# kilif_rev1.net
KiCad netlist of a schematic drawn in Altium Designer
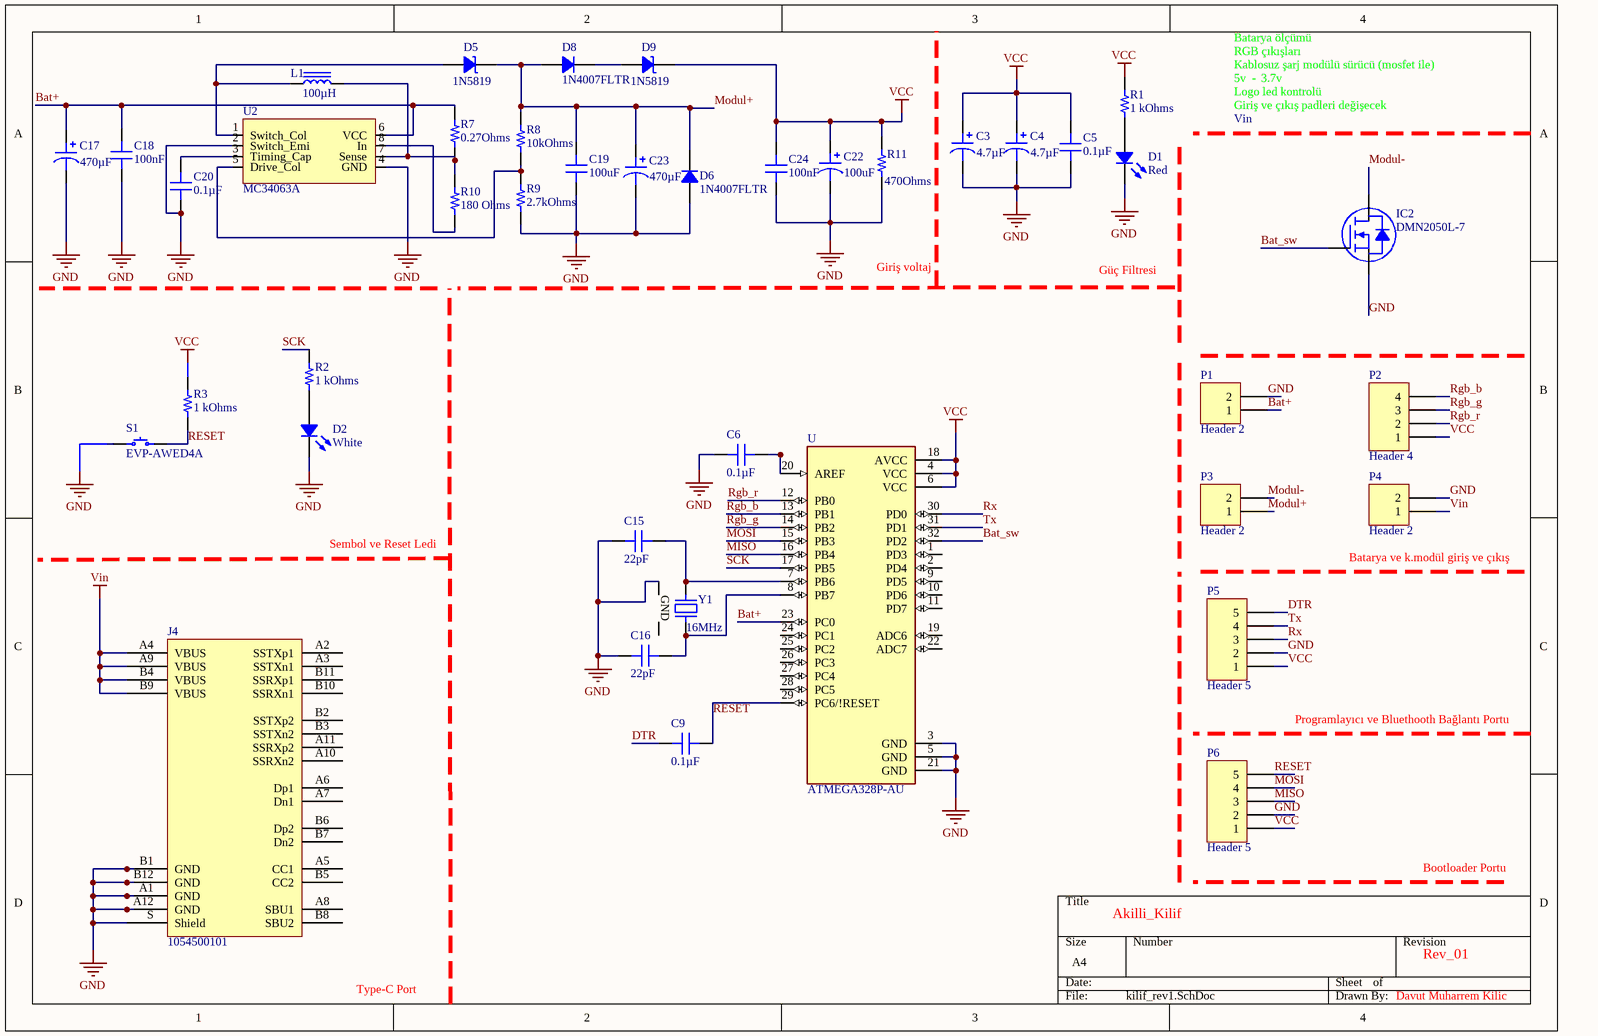
[diagram p0: kilif_rev1.SchDoc]

(export (version "E")
  (design (tool "Eeschema 10.0.6"))
  (components
    (comp (ref "C3")
      (value "4.7µF")
      (footprint "CAP POL 1206_3216")
      (description "CAP TANT POLY 4.7UF 10V 1206")
      (fields (field (name "PART NUMBER") "T55A475M010C0500") (field (name "MANUFACTURER") "Vishay Sprague"))
      (libsource (lib "Celestial Altium Library - altium_library") (part "Polarised Capacitor"))
    )
    (comp (ref "C4")
      (value "4.7µF")
      (footprint "CAP POL 1206_3216")
      (description "CAP TANT POLY 4.7UF 10V 1206")
      (fields (field (name "PART NUMBER") "T55A475M010C0500") (field (name "MANUFACTURER") "Vishay Sprague"))
      (libsource (lib "Celestial Altium Library - altium_library") (part "Polarised Capacitor"))
    )
    (comp (ref "C5")
      (value "0.1µF")
      (footprint "CAP 0603_1608")
      (description "CAP CER 0.1UF 50V X7R 0603")
      (fields (field (name "PART NUMBER") "C0603C104K5RAC7411") (field (name "MANUFACTURER") "KEMET"))
      (libsource (lib "Celestial Altium Library - altium_library") (part "Capacitor"))
    )
    (comp (ref "C6")
      (value "0.1µF")
      (footprint "CAP 0603_1608")
      (description "CAP CER 0.1UF 16V X7R 0603")
      (fields (field (name "PART NUMBER") "CS0603KRX7R7BB104") (field (name "MANUFACTURER") "Yageo"))
      (libsource (lib "Celestial Altium Library - altium_library") (part "Capacitor"))
    )
    (comp (ref "C9")
      (value "0.1µF")
      (footprint "CAP 0603_1608")
      (description "CAP CER 0.1UF 50V X7R 0603")
      (fields (field (name "PART NUMBER") "C0603C104K5RAC7411") (field (name "MANUFACTURER") "KEMET"))
      (libsource (lib "Celestial Altium Library - altium_library") (part "Capacitor"))
    )
    (comp (ref "C15")
      (value "22pF")
      (footprint "CAP 0603_1608")
      (description "CAP CER 22PfF 50V X7R 0603")
      (fields (field (name "PART NUMBER") "C0603C104K5RAC7411") (field (name "MANUFACTURER") "KEMET"))
      (libsource (lib "Celestial Altium Library - altium_library") (part "Capacitor"))
    )
    (comp (ref "C16")
      (value "22pF")
      (footprint "CAP 0603_1608")
      (description "CAP CER 22PF 50V X7R 0603")
      (fields (field (name "PART NUMBER") "C0603C104K5RAC7411") (field (name "MANUFACTURER") "KEMET"))
      (libsource (lib "Celestial Altium Library - altium_library") (part "Capacitor"))
    )
    (comp (ref "C17")
      (value "470µF")
      (footprint "CAP POL 1206_3216")
      (description "CAP TANT POLY 4.7UF 10V 1206")
      (fields (field (name "PART NUMBER") "T55A475M010C0500") (field (name "MANUFACTURER") "Vishay Sprague"))
      (libsource (lib "Celestial Altium Library - altium_library") (part "Polarised Capacitor"))
    )
    (comp (ref "C18")
      (value "100nF")
      (footprint "CAP 0603_1608")
      (description "CAP CER 0.1UF 50V X7R 0603")
      (fields (field (name "PART NUMBER") "C0603C104K5RAC7411") (field (name "MANUFACTURER") "KEMET"))
      (libsource (lib "Celestial Altium Library - altium_library") (part "Capacitor"))
    )
    (comp (ref "C19")
      (value "100uF")
      (footprint "CAP 0603_1608")
      (description "CAP CER 0.1UF 50V X7R 0603")
      (fields (field (name "PART NUMBER") "C0603C104K5RAC7411") (field (name "MANUFACTURER") "KEMET"))
      (libsource (lib "Celestial Altium Library - altium_library") (part "Capacitor"))
    )
    (comp (ref "C20")
      (value "0.1µF")
      (footprint "CAP 0603_1608")
      (description "CAP CER 0.1UF 50V X7R 0603")
      (fields (field (name "PART NUMBER") "C0603C104K5RAC7411") (field (name "MANUFACTURER") "KEMET"))
      (libsource (lib "Celestial Altium Library - altium_library") (part "Capacitor"))
    )
    (comp (ref "C22")
      (value "100uF")
      (footprint "CAP POL 1206_3216")
      (description "CAP TANT POLY 4.7UF 10V 1206")
      (fields (field (name "PART NUMBER") "T55A475M010C0500") (field (name "MANUFACTURER") "Vishay Sprague"))
      (libsource (lib "Celestial Altium Library - altium_library") (part "Polarised Capacitor"))
    )
    (comp (ref "C23")
      (value "470µF")
      (footprint "CAP POL 1206_3216")
      (description "CAP TANT POLY 4.7UF 10V 1206")
      (fields (field (name "PART NUMBER") "T55A475M010C0500") (field (name "MANUFACTURER") "Vishay Sprague"))
      (libsource (lib "Celestial Altium Library - altium_library") (part "Polarised Capacitor"))
    )
    (comp (ref "C24")
      (value "100nF")
      (footprint "CAP 0603_1608")
      (description "CAP CER 0.1UF 50V X7R 0603")
      (fields (field (name "PART NUMBER") "C0603C104K5RAC7411") (field (name "MANUFACTURER") "KEMET"))
      (libsource (lib "Celestial Altium Library - altium_library") (part "Capacitor"))
    )
    (comp (ref "D1")
      (value "Red")
      (footprint "LED 0805_2012 RED")
      (description "LED RED CLEAR 2SMD")
      (fields
        (field (name "PART NUMBER") "EAST2012RA1")
        (field (name "MANUFACTURER") "Everlight Electronics Co Ltd")
      )
      (libsource (lib "Celestial Altium Library - altium_library") (part "LED"))
    )
    (comp (ref "D2")
      (value "White")
      (footprint "LED 1206_3216")
      (description "LED WHITE 1206 SMD")
      (fields (field (name "PART NUMBER") "LTW-C230DS") (field (name "MANUFACTURER") "Lite-On Inc."))
      (libsource (lib "Celestial Altium Library - altium_library") (part "LED"))
    )
    (comp (ref "D5")
      (value "1N5819")
      (footprint "SMF DO-219AB")
      (description "TVS DIODE 45V 72.7V DO219AB")
      (fields
        (field (name "PART NUMBER") "SMF45A-E3-08")
        (field (name "MANUFACTURER") "Vishay Semiconductor Diodes Division")
      )
      (libsource (lib "Celestial Altium Library - altium_library") (part "DIODE TVS UNI"))
    )
    (comp (ref "D6")
      (value "1N4007FLTR")
      (footprint "SOD123F")
      (description "STANDARD RECTIFIER 1000V SOD-123")
      (fields (field (name "MANUFACTURER") "SMC Diode Solutions"))
      (libsource (lib "Celestial Altium Library - altium_library") (part "Diode"))
    )
    (comp (ref "D8")
      (value "1N4007FLTR")
      (footprint "SOD123F")
      (description "STANDARD RECTIFIER 1000V SOD-123")
      (fields (field (name "MANUFACTURER") "SMC Diode Solutions"))
      (libsource (lib "Celestial Altium Library - altium_library") (part "Diode"))
    )
    (comp (ref "D9")
      (value "1N5819")
      (footprint "SMF DO-219AB")
      (description "TVS DIODE 45V 72.7V DO219AB")
      (fields
        (field (name "PART NUMBER") "SMF45A-E3-08")
        (field (name "MANUFACTURER") "Vishay Semiconductor Diodes Division")
      )
      (libsource (lib "Celestial Altium Library - altium_library") (part "DIODE TVS UNI"))
    )
    (comp (ref "IC2")
      (value "DMN2050L-7")
      (footprint "DIODES SOT-23-3")
      (description "MOSFET N-CH 20V 5.9A SOT23-3")
      (fields (field (name "MANUFACTURER") "Diodes Incorporated"))
      (libsource (lib "Celestial Altium Library - altium_library") (part "DIODES INC MOSFET N-CH SOT-23-3"))
    )
    (comp (ref "J4")
      (value "1054500101")
      (footprint "Molex 1054500101")
      (description "CONN RCP USB3.1 TYPEC 24P SMD RA")
      (fields (field (name "MANUFACTURER") "Molex"))
      (libsource (lib "Celestial Altium Library - altium_library") (part "USB 3.0 Type C"))
    )
    (comp (ref "L1")
      (value "100µH")
      (footprint "TDK VLCF4028-2")
      (description "FIXED IND 100UH 330MA 670 MOHM")
      (fields
        (field (name "PART NUMBER") "VLCF5028T-101MR33-2")
        (field (name "MANUFACTURER") "TDK Corporation")
      )
      (libsource (lib "Celestial Altium Library - altium_library") (part "Inductor"))
    )
    (comp (ref "P1")
      (value "Header 2")
      (footprint "HDR1X2")
      (description "Header, 2-Pin")
      (fields (field (name "PUBLISHER") "Altium Limited"))
      (libsource (lib "Miscellaneous Connectors") (part "Header 2"))
    )
    (comp (ref "P2")
      (value "Header 4")
      (footprint "HDR1X4")
      (description "Header, 4-Pin")
      (fields (field (name "PUBLISHER") "Altium Limited"))
      (libsource (lib "Miscellaneous Connectors") (part "Header 4"))
    )
    (comp (ref "P3")
      (value "Header 2")
      (footprint "HDR1X2")
      (description "Header, 2-Pin")
      (fields (field (name "PUBLISHER") "Altium Limited"))
      (libsource (lib "Miscellaneous Connectors") (part "Header 2"))
    )
    (comp (ref "P4")
      (value "Header 2")
      (footprint "HDR1X2")
      (description "Header, 2-Pin")
      (fields (field (name "PUBLISHER") "Altium Limited"))
      (libsource (lib "Miscellaneous Connectors") (part "Header 2"))
    )
    (comp (ref "P5")
      (value "Header 5")
      (footprint "HDR1X5")
      (description "Header, 5-Pin")
      (fields (field (name "PUBLISHER") "Altium Limited"))
      (libsource (lib "Miscellaneous Connectors") (part "Header 5"))
    )
    (comp (ref "P6")
      (value "Header 5")
      (footprint "HDR1X5")
      (description "Header, 5-Pin")
      (fields (field (name "PUBLISHER") "Altium Limited"))
      (libsource (lib "Miscellaneous Connectors") (part "Header 5"))
    )
    (comp (ref "R1")
      (value "1 kOhms")
      (footprint "RES 0805_2012")
      (description "RES 1K OHM 1% 1/4W 0805")
      (fields
        (field (name "PART NUMBER") "RNCP0805FTD1K00")
        (field (name "MANUFACTURER") "Stackpole Electronics Inc")
      )
      (libsource (lib "Celestial Altium Library - altium_library") (part "Resistor"))
    )
    (comp (ref "R2")
      (value "1 kOhms")
      (footprint "RES 0805_2012")
      (description "RES 1K OHM 1% 1/4W 0805")
      (fields
        (field (name "PART NUMBER") "RNCP0805FTD1K00")
        (field (name "MANUFACTURER") "Stackpole Electronics Inc")
      )
      (libsource (lib "Celestial Altium Library - altium_library") (part "Resistor"))
    )
    (comp (ref "R3")
      (value "1 kOhms")
      (footprint "RES 0805_2012")
      (description "RES 1K OHM 1% 1/4W 0805")
      (fields
        (field (name "PART NUMBER") "RNCP0805FTD1K00")
        (field (name "MANUFACTURER") "Stackpole Electronics Inc")
      )
      (libsource (lib "Celestial Altium Library - altium_library") (part "Resistor"))
    )
    (comp (ref "R7")
      (value "0.27Ohms")
      (footprint "RES 0805_2012")
      (description "RES 1K OHM 1% 1/4W 0805")
      (fields
        (field (name "PART NUMBER") "RNCP0805FTD1K00")
        (field (name "MANUFACTURER") "Stackpole Electronics Inc")
      )
      (libsource (lib "Celestial Altium Library - altium_library") (part "Resistor"))
    )
    (comp (ref "R8")
      (value "10kOhms")
      (footprint "RES 0805_2012")
      (description "RES 1K OHM 1% 1/4W 0805")
      (fields
        (field (name "PART NUMBER") "RNCP0805FTD1K00")
        (field (name "MANUFACTURER") "Stackpole Electronics Inc")
      )
      (libsource (lib "Celestial Altium Library - altium_library") (part "Resistor"))
    )
    (comp (ref "R9")
      (value "2.7kOhms")
      (footprint "RES 0805_2012")
      (description "RES 1K OHM 1% 1/4W 0805")
      (fields
        (field (name "PART NUMBER") "RNCP0805FTD1K00")
        (field (name "MANUFACTURER") "Stackpole Electronics Inc")
      )
      (libsource (lib "Celestial Altium Library - altium_library") (part "Resistor"))
    )
    (comp (ref "R10")
      (value "180 Ohms")
      (footprint "RES 0805_2012")
      (description "RES 1K OHM 1% 1/4W 0805")
      (fields
        (field (name "PART NUMBER") "RNCP0805FTD1K00")
        (field (name "MANUFACTURER") "Stackpole Electronics Inc")
      )
      (libsource (lib "Celestial Altium Library - altium_library") (part "Resistor"))
    )
    (comp (ref "R11")
      (value "470Ohms")
      (footprint "RES 0805_2012")
      (description "RES 1K OHM 1% 1/4W 0805")
      (fields
        (field (name "PART NUMBER") "RNCP0805FTD1K00")
        (field (name "MANUFACTURER") "Stackpole Electronics Inc")
      )
      (libsource (lib "Celestial Altium Library - altium_library") (part "Resistor"))
    )
    (comp (ref "S1")
      (value "EVP-AWED4A")
      (footprint "PANASONIC EVPAW")
      (description "3.0MM X 2.0MM / 3.3N / 0.15MM ST")
      (fields (field (name "MANUFACTURER") "Panasonic Electronic Components"))
      (libsource (lib "Celestial Altium Library - altium_library") (part "SPST-NO 2 PIN"))
    )
    (comp (ref "U")
      (value "ATMEGA328P-AU")
      (footprint "QFP80P900X900X120-32N")
      (description "AVR AVRÂ® ATmega Microcontroller IC 8-Bit 20MHz 32KB _16K x 16_ FLASH 32-TQFP _7x7_")
      (fields (field (name "MF") "Microchip"))
      (libsource (lib "ATMEGA328P-AU") (part "ATMEGA328P-AU"))
    )
    (comp (ref "U2")
      (value "MC34063A")
      (footprint "MC34063A,SOIC127P600X140-8N")
      (description "1.5 A, Step-Up/Down/\r\nInverting Switching\r\nRegulators")
      (libsource (lib "Schlib1") (part "MC34063A"))
    )
    (comp (ref "Y1")
      (value "16MHz")
      (footprint "NDK NX3225SA")
      (description "CRYSTAL 16.0000MHZ 8PF SMD")
      (fields
        (field (name "PART NUMBER") "NX3225SA-16.000M-STD-CRS-2")
        (field (name "MANUFACTURER") "NDK America, Inc.")
      )
      (libsource (lib "Celestial Altium Library - altium_library") (part "NDK Crystal NX3225SA"))
    )
  )
  (nets
    (net (code "1") (name "/Bat+") (class "Default")
      (node (ref "C17") (pin "1") (pinfunction "1_1") (pintype "passive"))
      (node (ref "C18") (pin "2") (pinfunction "2_2") (pintype "passive"))
      (node (ref "P1") (pin "1") (pinfunction "1_1") (pintype "passive"))
      (node (ref "R7") (pin "2") (pinfunction "2_2") (pintype "passive"))
      (node (ref "U") (pin "23") (pinfunction "PC0_23") (pintype "bidirectional"))
      (node (ref "U2") (pin "6") (pinfunction "VCC_6") (pintype "passive"))
    )
    (net (code "2") (name "/Bat_sw") (class "Default")
      (node (ref "IC2") (pin "1") (pinfunction "G_1") (pintype "passive"))
      (node (ref "U") (pin "32") (pinfunction "PD2_32") (pintype "bidirectional"))
    )
    (net (code "3") (name "/DTR") (class "Default")
      (node (ref "C9") (pin "2") (pinfunction "2_2") (pintype "passive"))
      (node (ref "P5") (pin "5") (pinfunction "5_5") (pintype "passive"))
    )
    (net (code "4") (name "/MISO") (class "Default")
      (node (ref "P6") (pin "3") (pinfunction "3_3") (pintype "passive"))
      (node (ref "U") (pin "16") (pinfunction "PB4_16") (pintype "bidirectional"))
    )
    (net (code "5") (name "/MOSI") (class "Default")
      (node (ref "P6") (pin "4") (pinfunction "4_4") (pintype "passive"))
      (node (ref "U") (pin "15") (pinfunction "PB3_15") (pintype "bidirectional"))
    )
    (net (code "6") (name "/Modul+") (class "Default")
      (node (ref "C19") (pin "2") (pinfunction "2_2") (pintype "passive"))
      (node (ref "C23") (pin "1") (pinfunction "1_1") (pintype "passive"))
      (node (ref "D5") (pin "2") (pinfunction "2_2") (pintype "passive"))
      (node (ref "D6") (pin "2") (pinfunction "2_2") (pintype "passive"))
      (node (ref "D8") (pin "1") (pinfunction "1_1") (pintype "passive"))
      (node (ref "P3") (pin "1") (pinfunction "1_1") (pintype "passive"))
      (node (ref "R8") (pin "2") (pinfunction "2_2") (pintype "passive"))
    )
    (net (code "7") (name "/Modul-") (class "Default")
      (node (ref "IC2") (pin "3") (pinfunction "D_3") (pintype "passive"))
      (node (ref "P3") (pin "2") (pinfunction "2_2") (pintype "passive"))
    )
    (net (code "8") (name "/RESET") (class "Default")
      (node (ref "C9") (pin "1") (pinfunction "1_1") (pintype "passive"))
      (node (ref "P6") (pin "5") (pinfunction "5_5") (pintype "passive"))
      (node (ref "R3") (pin "1") (pinfunction "1_1") (pintype "passive"))
      (node (ref "S1") (pin "2") (pinfunction "2_2") (pintype "passive"))
      (node (ref "U") (pin "29") (pinfunction "PC6/!RESET_29") (pintype "bidirectional"))
    )
    (net (code "9") (name "/Rgb_b") (class "Default")
      (node (ref "P2") (pin "4") (pinfunction "4_4") (pintype "passive"))
      (node (ref "U") (pin "13") (pinfunction "PB1_13") (pintype "bidirectional"))
    )
    (net (code "10") (name "/Rgb_g") (class "Default")
      (node (ref "P2") (pin "3") (pinfunction "3_3") (pintype "passive"))
      (node (ref "U") (pin "14") (pinfunction "PB2_14") (pintype "bidirectional"))
    )
    (net (code "11") (name "/Rgb_r") (class "Default")
      (node (ref "P2") (pin "2") (pinfunction "2_2") (pintype "passive"))
      (node (ref "U") (pin "12") (pinfunction "PB0_12") (pintype "bidirectional"))
    )
    (net (code "12") (name "/Rx") (class "Default")
      (node (ref "P5") (pin "3") (pinfunction "3_3") (pintype "passive"))
      (node (ref "U") (pin "30") (pinfunction "PD0_30") (pintype "bidirectional"))
    )
    (net (code "13") (name "/SCK") (class "Default")
      (node (ref "R2") (pin "2") (pinfunction "2_2") (pintype "passive"))
      (node (ref "U") (pin "17") (pinfunction "PB5_17") (pintype "bidirectional"))
    )
    (net (code "14") (name "/Tx") (class "Default")
      (node (ref "P5") (pin "4") (pinfunction "4_4") (pintype "passive"))
      (node (ref "U") (pin "31") (pinfunction "PD1_31") (pintype "bidirectional"))
    )
    (net (code "15") (name "GND") (class "Default")
      (node (ref "C15") (pin "2") (pinfunction "2_2") (pintype "passive"))
      (node (ref "C16") (pin "2") (pinfunction "2_2") (pintype "passive"))
      (node (ref "C17") (pin "2") (pinfunction "2_2") (pintype "passive"))
      (node (ref "C18") (pin "1") (pinfunction "1_1") (pintype "passive"))
      (node (ref "C19") (pin "1") (pinfunction "1_1") (pintype "passive"))
      (node (ref "C20") (pin "1") (pinfunction "1_1") (pintype "passive"))
      (node (ref "C22") (pin "2") (pinfunction "2_2") (pintype "passive"))
      (node (ref "C23") (pin "2") (pinfunction "2_2") (pintype "passive"))
      (node (ref "C24") (pin "1") (pinfunction "1_1") (pintype "passive"))
      (node (ref "C3") (pin "2") (pinfunction "2_2") (pintype "passive"))
      (node (ref "C4") (pin "2") (pinfunction "2_2") (pintype "passive"))
      (node (ref "C5") (pin "1") (pinfunction "1_1") (pintype "passive"))
      (node (ref "C6") (pin "1") (pinfunction "1_1") (pintype "passive"))
      (node (ref "D1") (pin "2") (pinfunction "2_2") (pintype "passive"))
      (node (ref "D2") (pin "2") (pinfunction "2_2") (pintype "passive"))
      (node (ref "D6") (pin "1") (pinfunction "1_1") (pintype "passive"))
      (node (ref "IC2") (pin "2") (pinfunction "S_2") (pintype "passive"))
      (node (ref "J4") (pin "A1") (pinfunction "GND_A1") (pintype "passive"))
      (node (ref "J4") (pin "A12") (pinfunction "GND_A12") (pintype "passive"))
      (node (ref "J4") (pin "B1") (pinfunction "GND_B1") (pintype "passive"))
      (node (ref "J4") (pin "B12") (pinfunction "GND_B12") (pintype "passive"))
      (node (ref "J4") (pin "S") (pinfunction "Shield_S") (pintype "passive"))
      (node (ref "P1") (pin "2") (pinfunction "2_2") (pintype "passive"))
      (node (ref "P4") (pin "2") (pinfunction "2_2") (pintype "passive"))
      (node (ref "P5") (pin "2") (pinfunction "2_2") (pintype "passive"))
      (node (ref "P6") (pin "2") (pinfunction "2_2") (pintype "passive"))
      (node (ref "R11") (pin "1") (pinfunction "1_1") (pintype "passive"))
      (node (ref "R9") (pin "1") (pinfunction "1_1") (pintype "passive"))
      (node (ref "S1") (pin "1") (pinfunction "1_1") (pintype "passive"))
      (node (ref "U") (pin "21") (pinfunction "GND_21") (pintype "power_in"))
      (node (ref "U") (pin "3") (pinfunction "GND_3") (pintype "power_in"))
      (node (ref "U") (pin "5") (pinfunction "GND_5") (pintype "power_in"))
      (node (ref "U2") (pin "2") (pinfunction "Switch_Emi_2") (pintype "passive"))
      (node (ref "U2") (pin "4") (pinfunction "GND_4") (pintype "passive"))
      (node (ref "Y1") (pin "4") (pinfunction "GND_4") (pintype "passive"))
    )
    (net (code "16") (name "Net-(D1-Pad1)") (class "Default")
      (node (ref "D1") (pin "1") (pinfunction "1_1") (pintype "passive"))
      (node (ref "R1") (pin "1") (pinfunction "1_1") (pintype "passive"))
    )
    (net (code "17") (name "Net-(D2-Pad1)") (class "Default")
      (node (ref "D2") (pin "1") (pinfunction "1_1") (pintype "passive"))
      (node (ref "R2") (pin "1") (pinfunction "1_1") (pintype "passive"))
    )
    (net (code "18") (name "Net-(D8-Pad2)") (class "Default")
      (node (ref "D8") (pin "2") (pinfunction "2_2") (pintype "passive"))
      (node (ref "D9") (pin "1") (pinfunction "1_1") (pintype "passive"))
    )
    (net (code "19") (name "Net-(U-AREF)") (class "Default")
      (node (ref "C6") (pin "2") (pinfunction "2_2") (pintype "passive"))
      (node (ref "U") (pin "20") (pinfunction "AREF_20") (pintype "input"))
    )
    (net (code "20") (name "Net-(U-PB6)") (class "Default")
      (node (ref "C15") (pin "1") (pinfunction "1_1") (pintype "passive"))
      (node (ref "U") (pin "7") (pinfunction "PB6_7") (pintype "bidirectional"))
      (node (ref "Y1") (pin "1") (pinfunction "1_1") (pintype "passive"))
    )
    (net (code "21") (name "Net-(U-PB7)") (class "Default")
      (node (ref "C16") (pin "1") (pinfunction "1_1") (pintype "passive"))
      (node (ref "U") (pin "8") (pinfunction "PB7_8") (pintype "bidirectional"))
      (node (ref "Y1") (pin "3") (pinfunction "3_3") (pintype "passive"))
    )
    (net (code "22") (name "Net-(U2-Drive_Col)") (class "Default")
      (node (ref "R8") (pin "1") (pinfunction "1_1") (pintype "passive"))
      (node (ref "R9") (pin "2") (pinfunction "2_2") (pintype "passive"))
      (node (ref "U2") (pin "5") (pinfunction "Drive_Col_5") (pintype "passive"))
    )
    (net (code "23") (name "Net-(U2-In)") (class "Default")
      (node (ref "R10") (pin "1") (pinfunction "1_1") (pintype "passive"))
      (node (ref "U2") (pin "8") (pinfunction "In_8") (pintype "passive"))
    )
    (net (code "24") (name "Net-(U2-Sense)") (class "Default")
      (node (ref "L1") (pin "2") (pinfunction "2_2") (pintype "passive"))
      (node (ref "R10") (pin "2") (pinfunction "2_2") (pintype "passive"))
      (node (ref "R7") (pin "1") (pinfunction "1_1") (pintype "passive"))
      (node (ref "U2") (pin "7") (pinfunction "Sense_7") (pintype "passive"))
    )
    (net (code "25") (name "Net-(U2-Switch_Col)") (class "Default")
      (node (ref "D5") (pin "1") (pinfunction "1_1") (pintype "passive"))
      (node (ref "L1") (pin "1") (pinfunction "1_1") (pintype "passive"))
      (node (ref "U2") (pin "1") (pinfunction "Switch_Col_1") (pintype "passive"))
    )
    (net (code "26") (name "Net-(U2-Timing_Cap)") (class "Default")
      (node (ref "C20") (pin "2") (pinfunction "2_2") (pintype "passive"))
      (node (ref "U2") (pin "3") (pinfunction "Timing_Cap_3") (pintype "passive"))
    )
    (net (code "27") (name "VCC") (class "Default")
      (node (ref "C22") (pin "1") (pinfunction "1_1") (pintype "passive"))
      (node (ref "C24") (pin "2") (pinfunction "2_2") (pintype "passive"))
      (node (ref "C3") (pin "1") (pinfunction "1_1") (pintype "passive"))
      (node (ref "C4") (pin "1") (pinfunction "1_1") (pintype "passive"))
      (node (ref "C5") (pin "2") (pinfunction "2_2") (pintype "passive"))
      (node (ref "D9") (pin "2") (pinfunction "2_2") (pintype "passive"))
      (node (ref "P2") (pin "1") (pinfunction "1_1") (pintype "passive"))
      (node (ref "P5") (pin "1") (pinfunction "1_1") (pintype "passive"))
      (node (ref "P6") (pin "1") (pinfunction "1_1") (pintype "passive"))
      (node (ref "R1") (pin "2") (pinfunction "2_2") (pintype "passive"))
      (node (ref "R11") (pin "2") (pinfunction "2_2") (pintype "passive"))
      (node (ref "R3") (pin "2") (pinfunction "2_2") (pintype "passive"))
      (node (ref "U") (pin "18") (pinfunction "AVCC_18") (pintype "power_in"))
      (node (ref "U") (pin "4") (pinfunction "VCC_4") (pintype "power_in"))
      (node (ref "U") (pin "6") (pinfunction "VCC_6") (pintype "power_in"))
    )
    (net (code "28") (name "Vin") (class "Default")
      (node (ref "J4") (pin "A4") (pinfunction "VBUS_A4") (pintype "passive"))
      (node (ref "J4") (pin "A9") (pinfunction "VBUS_A9") (pintype "passive"))
      (node (ref "J4") (pin "B4") (pinfunction "VBUS_B4") (pintype "passive"))
      (node (ref "J4") (pin "B9") (pinfunction "VBUS_B9") (pintype "passive"))
      (node (ref "P4") (pin "1") (pinfunction "1_1") (pintype "passive"))
    )
    (net (code "29") (name "unconnected-(J4-CC1-PadA5)") (class "Default")
      (node (ref "J4") (pin "A5") (pinfunction "CC1_A5") (pintype "passive"))
    )
    (net (code "30") (name "unconnected-(J4-CC2-PadB5)") (class "Default")
      (node (ref "J4") (pin "B5") (pinfunction "CC2_B5") (pintype "passive"))
    )
    (net (code "31") (name "unconnected-(J4-Dn1-PadA7)") (class "Default")
      (node (ref "J4") (pin "A7") (pinfunction "Dn1_A7") (pintype "passive"))
    )
    (net (code "32") (name "unconnected-(J4-Dn2-PadB7)") (class "Default")
      (node (ref "J4") (pin "B7") (pinfunction "Dn2_B7") (pintype "passive"))
    )
    (net (code "33") (name "unconnected-(J4-Dp1-PadA6)") (class "Default")
      (node (ref "J4") (pin "A6") (pinfunction "Dp1_A6") (pintype "passive"))
    )
    (net (code "34") (name "unconnected-(J4-Dp2-PadB6)") (class "Default")
      (node (ref "J4") (pin "B6") (pinfunction "Dp2_B6") (pintype "passive"))
    )
    (net (code "35") (name "unconnected-(J4-SBU1-PadA8)") (class "Default")
      (node (ref "J4") (pin "A8") (pinfunction "SBU1_A8") (pintype "passive"))
    )
    (net (code "36") (name "unconnected-(J4-SBU2-PadB8)") (class "Default")
      (node (ref "J4") (pin "B8") (pinfunction "SBU2_B8") (pintype "passive"))
    )
    (net (code "37") (name "unconnected-(J4-SSRXn1-PadB10)") (class "Default")
      (node (ref "J4") (pin "B10") (pinfunction "SSRXn1_B10") (pintype "passive"))
    )
    (net (code "38") (name "unconnected-(J4-SSRXn2-PadA10)") (class "Default")
      (node (ref "J4") (pin "A10") (pinfunction "SSRXn2_A10") (pintype "passive"))
    )
    (net (code "39") (name "unconnected-(J4-SSRXp1-PadB11)") (class "Default")
      (node (ref "J4") (pin "B11") (pinfunction "SSRXp1_B11") (pintype "passive"))
    )
    (net (code "40") (name "unconnected-(J4-SSRXp2-PadA11)") (class "Default")
      (node (ref "J4") (pin "A11") (pinfunction "SSRXp2_A11") (pintype "passive"))
    )
    (net (code "41") (name "unconnected-(J4-SSTXn1-PadA3)") (class "Default")
      (node (ref "J4") (pin "A3") (pinfunction "SSTXn1_A3") (pintype "passive"))
    )
    (net (code "42") (name "unconnected-(J4-SSTXn2-PadB3)") (class "Default")
      (node (ref "J4") (pin "B3") (pinfunction "SSTXn2_B3") (pintype "passive"))
    )
    (net (code "43") (name "unconnected-(J4-SSTXp1-PadA2)") (class "Default")
      (node (ref "J4") (pin "A2") (pinfunction "SSTXp1_A2") (pintype "passive"))
    )
    (net (code "44") (name "unconnected-(J4-SSTXp2-PadB2)") (class "Default")
      (node (ref "J4") (pin "B2") (pinfunction "SSTXp2_B2") (pintype "passive"))
    )
    (net (code "45") (name "unconnected-(U-ADC6-Pad19)") (class "Default")
      (node (ref "U") (pin "19") (pinfunction "ADC6_19") (pintype "bidirectional"))
    )
    (net (code "46") (name "unconnected-(U-ADC7-Pad22)") (class "Default")
      (node (ref "U") (pin "22") (pinfunction "ADC7_22") (pintype "bidirectional"))
    )
    (net (code "47") (name "unconnected-(U-PC1-Pad24)") (class "Default")
      (node (ref "U") (pin "24") (pinfunction "PC1_24") (pintype "bidirectional"))
    )
    (net (code "48") (name "unconnected-(U-PC2-Pad25)") (class "Default")
      (node (ref "U") (pin "25") (pinfunction "PC2_25") (pintype "bidirectional"))
    )
    (net (code "49") (name "unconnected-(U-PC3-Pad26)") (class "Default")
      (node (ref "U") (pin "26") (pinfunction "PC3_26") (pintype "bidirectional"))
    )
    (net (code "50") (name "unconnected-(U-PC4-Pad27)") (class "Default")
      (node (ref "U") (pin "27") (pinfunction "PC4_27") (pintype "bidirectional"))
    )
    (net (code "51") (name "unconnected-(U-PC5-Pad28)") (class "Default")
      (node (ref "U") (pin "28") (pinfunction "PC5_28") (pintype "bidirectional"))
    )
    (net (code "52") (name "unconnected-(U-PD3-Pad1)") (class "Default")
      (node (ref "U") (pin "1") (pinfunction "PD3_1") (pintype "bidirectional"))
    )
    (net (code "53") (name "unconnected-(U-PD4-Pad2)") (class "Default")
      (node (ref "U") (pin "2") (pinfunction "PD4_2") (pintype "bidirectional"))
    )
    (net (code "54") (name "unconnected-(U-PD5-Pad9)") (class "Default")
      (node (ref "U") (pin "9") (pinfunction "PD5_9") (pintype "bidirectional"))
    )
    (net (code "55") (name "unconnected-(U-PD6-Pad10)") (class "Default")
      (node (ref "U") (pin "10") (pinfunction "PD6_10") (pintype "bidirectional"))
    )
    (net (code "56") (name "unconnected-(U-PD7-Pad11)") (class "Default")
      (node (ref "U") (pin "11") (pinfunction "PD7_11") (pintype "bidirectional"))
    )
    (net (code "57") (name "unconnected-(Y1-GND-Pad2)") (class "Default")
      (node (ref "Y1") (pin "2") (pinfunction "GND_2") (pintype "passive"))
    )
  )
)
